# r8_2.net
KiCad netlist of a schematic drawn in EAGLE
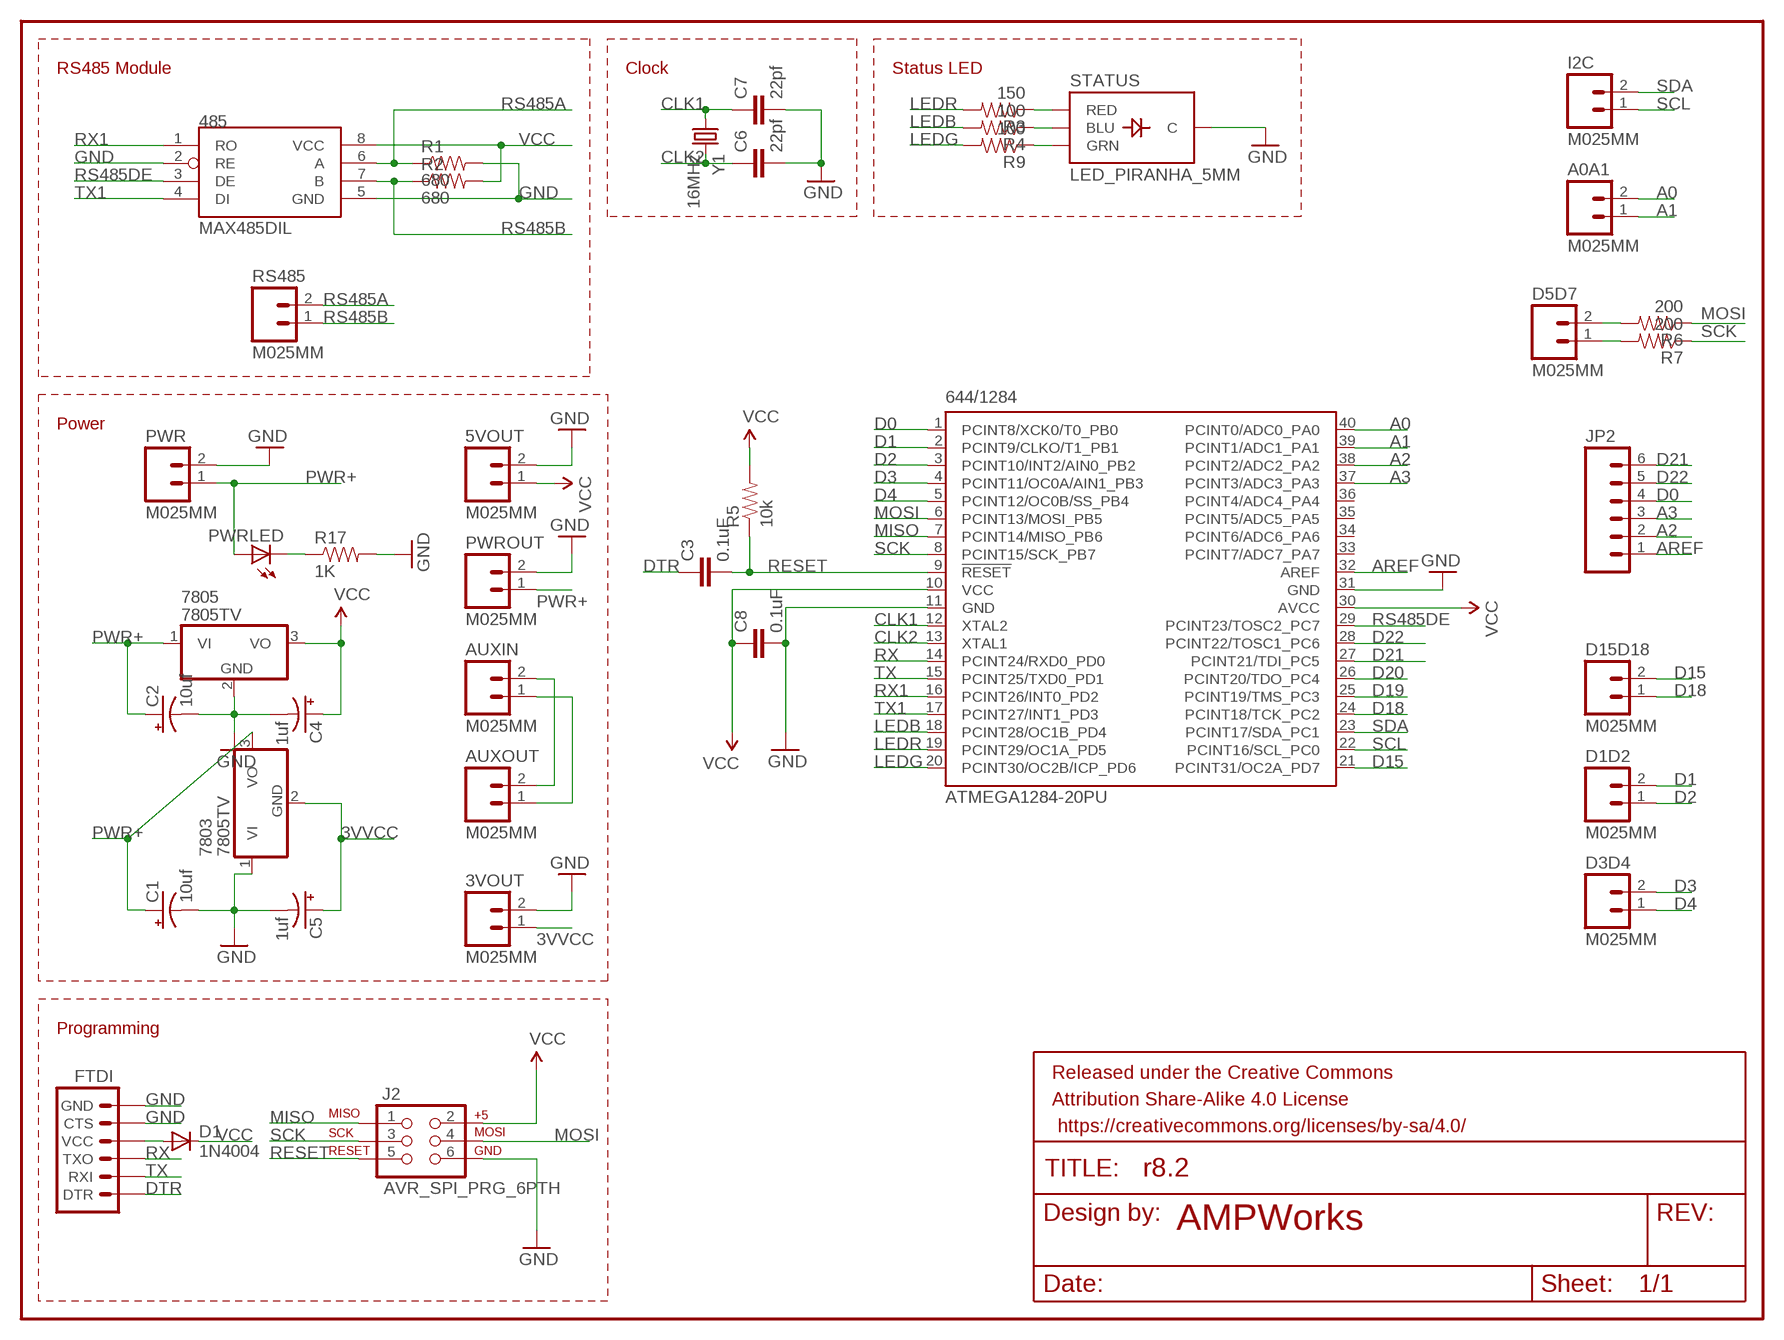
[diagram p0: schematic, sheet 1]

(export (version "E")
  (design (tool "Eeschema 10.0.6"))
  (components
    (comp (ref "3VOUT")
      (value "M025MM")
      (footprint "eagle-import:SCREWTERMINAL-5MM-2")
      (libsource (lib "eagle-import") (part "M025MM"))
    )
    (comp (ref "5VOUT")
      (value "M025MM")
      (footprint "eagle-import:SCREWTERMINAL-5MM-2")
      (libsource (lib "eagle-import") (part "M025MM"))
    )
    (comp (ref "485")
      (value "MAX485DIL")
      (footprint "eagle-import:DIL08")
      (libsource (lib "eagle-import") (part "MAX485DIL"))
    )
    (comp (ref "644/1284")
      (value "ATMEGA1284-20PU")
      (footprint "eagle-import:DIL40")
      (fields (field (name "MPN") "ATMEGA644-20PU"))
      (libsource (lib "eagle-import") (part "ATMEGA644-PU20"))
    )
    (comp (ref "7803")
      (value "7805TV")
      (footprint "eagle-import:TO220V")
      (libsource (lib "eagle-import") (part "78TV05"))
    )
    (comp (ref "7805")
      (value "7805TV")
      (footprint "eagle-import:TO220V")
      (libsource (lib "eagle-import") (part "78TV05"))
    )
    (comp (ref "A0A1")
      (value "M025MM")
      (footprint "eagle-import:SCREWTERMINAL-5MM-2")
      (libsource (lib "eagle-import") (part "M025MM"))
    )
    (comp (ref "AUXIN")
      (value "M025MM")
      (footprint "eagle-import:SCREWTERMINAL-5MM-2")
      (libsource (lib "eagle-import") (part "M025MM"))
    )
    (comp (ref "AUXOUT")
      (value "M025MM")
      (footprint "eagle-import:SCREWTERMINAL-5MM-2")
      (libsource (lib "eagle-import") (part "M025MM"))
    )
    (comp (ref "C1")
      (value "10uf")
      (footprint "eagle-import:CPOL-RADIAL-10UF-25V")
      (libsource (lib "eagle-import") (part "CAP_POLPTH2"))
    )
    (comp (ref "C2")
      (value "10uf")
      (footprint "eagle-import:CPOL-RADIAL-10UF-25V")
      (libsource (lib "eagle-import") (part "CAP_POLPTH2"))
    )
    (comp (ref "C3")
      (value "0.1uF")
      (footprint "eagle-import:CAP-PTH-SMALL")
      (libsource (lib "eagle-import") (part "CAPPTH"))
    )
    (comp (ref "C4")
      (value "1uf")
      (footprint "eagle-import:CPOL-RADIAL-10UF-25V")
      (libsource (lib "eagle-import") (part "CAP_POLPTH2"))
    )
    (comp (ref "C5")
      (value "1uf")
      (footprint "eagle-import:CPOL-RADIAL-10UF-25V")
      (libsource (lib "eagle-import") (part "CAP_POLPTH2"))
    )
    (comp (ref "C6")
      (value "22pf")
      (footprint "eagle-import:CAP-PTH-SMALL")
      (libsource (lib "eagle-import") (part "CAPPTH"))
    )
    (comp (ref "C7")
      (value "22pf")
      (footprint "eagle-import:CAP-PTH-SMALL")
      (libsource (lib "eagle-import") (part "CAPPTH"))
    )
    (comp (ref "C8")
      (value "0.1uF")
      (footprint "eagle-import:CAP-PTH-SMALL")
      (libsource (lib "eagle-import") (part "CAPPTH"))
    )
    (comp (ref "D1")
      (value "1N4004")
      (footprint "eagle-import:DO41-10")
      (libsource (lib "eagle-import") (part "1N4004"))
    )
    (comp (ref "D1D2")
      (value "M025MM")
      (footprint "eagle-import:SCREWTERMINAL-5MM-2")
      (libsource (lib "eagle-import") (part "M025MM"))
    )
    (comp (ref "D3D4")
      (value "M025MM")
      (footprint "eagle-import:SCREWTERMINAL-5MM-2")
      (libsource (lib "eagle-import") (part "M025MM"))
    )
    (comp (ref "D5D7")
      (value "M025MM")
      (footprint "eagle-import:SCREWTERMINAL-5MM-2")
      (libsource (lib "eagle-import") (part "M025MM"))
    )
    (comp (ref "D15D18")
      (value "M025MM")
      (footprint "eagle-import:SCREWTERMINAL-5MM-2")
      (libsource (lib "eagle-import") (part "M025MM"))
    )
    (comp (ref "FRAME1")
      (value "FRAME-LETTER")
      (footprint "eagle-import:CREATIVE_COMMONS")
      (libsource (lib "eagle-import") (part "FRAME-LETTER"))
    )
    (comp (ref "FTDI")
      (value "ARDUINO_SERIAL_PROGRAMPTH")
      (footprint "eagle-import:1X06")
      (libsource (lib "eagle-import") (part "ARDUINO_SERIAL_PROGRAMPTH"))
    )
    (comp (ref "I2C")
      (value "M025MM")
      (footprint "eagle-import:SCREWTERMINAL-5MM-2")
      (libsource (lib "eagle-import") (part "M025MM"))
    )
    (comp (ref "J2")
      (value "AVR_SPI_PRG_6PTH")
      (footprint "eagle-import:2X3")
      (libsource (lib "eagle-import") (part "AVR_SPI_PRG_6PTH"))
    )
    (comp (ref "JP2")
      (value "M06NO_SILK")
      (footprint "eagle-import:1X06_NO_SILK")
      (libsource (lib "eagle-import") (part "M06NO_SILK"))
    )
    (comp (ref "PWR")
      (value "M025MM")
      (footprint "eagle-import:SCREWTERMINAL-5MM-2")
      (libsource (lib "eagle-import") (part "M025MM"))
    )
    (comp (ref "PWRLED")
      (value "LED5MM")
      (footprint "eagle-import:LED5MM")
      (libsource (lib "eagle-import") (part "LED5MM"))
    )
    (comp (ref "PWROUT")
      (value "M025MM")
      (footprint "eagle-import:SCREWTERMINAL-5MM-2")
      (libsource (lib "eagle-import") (part "M025MM"))
    )
    (comp (ref "R1")
      (value "680")
      (footprint "eagle-import:AXIAL-0.4")
      (libsource (lib "eagle-import") (part "SparkFun-Resistors_RESISTORPTH-1/4W"))
    )
    (comp (ref "R2")
      (value "680")
      (footprint "eagle-import:AXIAL-0.4")
      (libsource (lib "eagle-import") (part "SparkFun-Resistors_RESISTORPTH-1/4W"))
    )
    (comp (ref "R3")
      (value "150")
      (footprint "eagle-import:AXIAL-0.4")
      (libsource (lib "eagle-import") (part "RESISTORPTH-1/4W"))
    )
    (comp (ref "R4")
      (value "100")
      (footprint "eagle-import:AXIAL-0.4")
      (libsource (lib "eagle-import") (part "RESISTORPTH-1/4W"))
    )
    (comp (ref "R5")
      (value "10k")
      (footprint "eagle-import:AXIAL-0.4")
      (libsource (lib "eagle-import") (part "RESISTORPTH-1/4W"))
    )
    (comp (ref "R6")
      (value "200")
      (footprint "eagle-import:AXIAL-0.4")
      (libsource (lib "eagle-import") (part "RESISTORPTH-1/4W"))
    )
    (comp (ref "R7")
      (value "200")
      (footprint "eagle-import:AXIAL-0.4")
      (libsource (lib "eagle-import") (part "RESISTORPTH-1/4W"))
    )
    (comp (ref "R9")
      (value "100")
      (footprint "eagle-import:AXIAL-0.4")
      (libsource (lib "eagle-import") (part "RESISTORPTH-1/4W"))
    )
    (comp (ref "R17")
      (value "1K")
      (footprint "eagle-import:AXIAL-0.4")
      (libsource (lib "eagle-import") (part "SparkFun-Resistors_RESISTORPTH-1/4W"))
    )
    (comp (ref "RS485")
      (value "M025MM")
      (footprint "eagle-import:SCREWTERMINAL-5MM-2")
      (libsource (lib "eagle-import") (part "M025MM"))
    )
    (comp (ref "STATUS")
      (value "LED_PIRANHA_5MM")
      (footprint "eagle-import:LED_PIRANHA_5MM")
      (libsource (lib "eagle-import") (part "LED_PIRANHA_5MM"))
    )
    (comp (ref "Y1")
      (value "16MHz")
      (footprint "eagle-import:HC49US")
      (libsource (lib "eagle-import") (part "CRYSTALHC49US"))
    )
  )
  (nets
    (net (code "1") (name "/3VVCC") (class "Default")
      (node (ref "3VOUT") (pin "1") (pinfunction "1_1") (pintype "passive"))
      (node (ref "7803") (pin "2") (pinfunction "GND_2") (pintype "passive"))
      (node (ref "C5") (pin "1") (pinfunction "+_1") (pintype "passive"))
    )
    (net (code "2") (name "/A0") (class "Default")
      (node (ref "644/1284") (pin "40") (pinfunction "PCINT0/ADC0_PA0_40") (pintype "bidirectional"))
      (node (ref "A0A1") (pin "2") (pinfunction "2_2") (pintype "passive"))
    )
    (net (code "3") (name "/A1") (class "Default")
      (node (ref "644/1284") (pin "39") (pinfunction "PCINT1/ADC1_PA1_39") (pintype "bidirectional"))
      (node (ref "A0A1") (pin "1") (pinfunction "1_1") (pintype "passive"))
    )
    (net (code "4") (name "/A2") (class "Default")
      (node (ref "644/1284") (pin "38") (pinfunction "PCINT2/ADC2_PA2_38") (pintype "bidirectional"))
      (node (ref "JP2") (pin "2") (pinfunction "2_2") (pintype "passive"))
    )
    (net (code "5") (name "/A3") (class "Default")
      (node (ref "644/1284") (pin "37") (pinfunction "PCINT3/ADC3_PA3_37") (pintype "bidirectional"))
      (node (ref "JP2") (pin "3") (pinfunction "3_3") (pintype "passive"))
    )
    (net (code "6") (name "/AREF") (class "Default")
      (node (ref "644/1284") (pin "32") (pinfunction "AREF_32") (pintype "passive"))
      (node (ref "JP2") (pin "1") (pinfunction "1_1") (pintype "passive"))
    )
    (net (code "7") (name "/CLK1") (class "Default")
      (node (ref "644/1284") (pin "12") (pinfunction "XTAL2_12") (pintype "output"))
      (node (ref "C7") (pin "1") (pinfunction "1_1") (pintype "passive"))
      (node (ref "Y1") (pin "1") (pinfunction "1_1") (pintype "passive"))
    )
    (net (code "8") (name "/CLK2") (class "Default")
      (node (ref "644/1284") (pin "13") (pinfunction "XTAL1_13") (pintype "input"))
      (node (ref "C6") (pin "1") (pinfunction "1_1") (pintype "passive"))
      (node (ref "Y1") (pin "2") (pinfunction "2_2") (pintype "passive"))
    )
    (net (code "9") (name "/D0") (class "Default")
      (node (ref "644/1284") (pin "1") (pinfunction "PCINT8/XCK0/T0_PB0_1") (pintype "bidirectional"))
      (node (ref "JP2") (pin "4") (pinfunction "4_4") (pintype "passive"))
    )
    (net (code "10") (name "/D1") (class "Default")
      (node (ref "644/1284") (pin "2") (pinfunction "PCINT9/CLKO/T1_PB1_2") (pintype "bidirectional"))
      (node (ref "D1D2") (pin "2") (pinfunction "2_2") (pintype "passive"))
    )
    (net (code "11") (name "/D2") (class "Default")
      (node (ref "644/1284") (pin "3") (pinfunction "PCINT10/INT2/AIN0_PB2_3") (pintype "bidirectional"))
      (node (ref "D1D2") (pin "1") (pinfunction "1_1") (pintype "passive"))
    )
    (net (code "12") (name "/D3") (class "Default")
      (node (ref "644/1284") (pin "4") (pinfunction "PCINT11/OC0A/AIN1_PB3_4") (pintype "bidirectional"))
      (node (ref "D3D4") (pin "2") (pinfunction "2_2") (pintype "passive"))
    )
    (net (code "13") (name "/D4") (class "Default")
      (node (ref "644/1284") (pin "5") (pinfunction "PCINT12/OC0B/SS_PB4_5") (pintype "bidirectional"))
      (node (ref "D3D4") (pin "1") (pinfunction "1_1") (pintype "passive"))
    )
    (net (code "14") (name "/D15") (class "Default")
      (node (ref "644/1284") (pin "21") (pinfunction "PCINT31/OC2A_PD7_21") (pintype "bidirectional"))
      (node (ref "D15D18") (pin "2") (pinfunction "2_2") (pintype "passive"))
    )
    (net (code "15") (name "/D18") (class "Default")
      (node (ref "644/1284") (pin "24") (pinfunction "PCINT18/TCK_PC2_24") (pintype "bidirectional"))
      (node (ref "D15D18") (pin "1") (pinfunction "1_1") (pintype "passive"))
    )
    (net (code "16") (name "/D19") (class "Default")
      (node (ref "644/1284") (pin "25") (pinfunction "PCINT19/TMS_PC3_25") (pintype "bidirectional"))
    )
    (net (code "17") (name "/D20") (class "Default")
      (node (ref "644/1284") (pin "26") (pinfunction "PCINT20/TDO_PC4_26") (pintype "bidirectional"))
    )
    (net (code "18") (name "/D21") (class "Default")
      (node (ref "644/1284") (pin "27") (pinfunction "PCINT21/TDI_PC5_27") (pintype "bidirectional"))
      (node (ref "JP2") (pin "6") (pinfunction "6_6") (pintype "passive"))
    )
    (net (code "19") (name "/D22") (class "Default")
      (node (ref "644/1284") (pin "28") (pinfunction "PCINT22/TOSC1_PC6_28") (pintype "bidirectional"))
      (node (ref "JP2") (pin "5") (pinfunction "5_5") (pintype "passive"))
    )
    (net (code "20") (name "/DTR") (class "Default")
      (node (ref "C3") (pin "1") (pinfunction "1_1") (pintype "passive"))
      (node (ref "FTDI") (pin "DTR") (pinfunction "DTR_DTR") (pintype "passive"))
    )
    (net (code "21") (name "/LEDB") (class "Default")
      (node (ref "644/1284") (pin "18") (pinfunction "PCINT28/OC1B_PD4_18") (pintype "bidirectional"))
      (node (ref "R4") (pin "P$2") (pinfunction "2_P$2") (pintype "passive"))
    )
    (net (code "22") (name "/LEDG") (class "Default")
      (node (ref "644/1284") (pin "20") (pinfunction "PCINT30/OC2B/ICP_PD6_20") (pintype "bidirectional"))
      (node (ref "R9") (pin "P$2") (pinfunction "2_P$2") (pintype "passive"))
    )
    (net (code "23") (name "/LEDR") (class "Default")
      (node (ref "644/1284") (pin "19") (pinfunction "PCINT29/OC1A_PD5_19") (pintype "bidirectional"))
      (node (ref "R3") (pin "P$2") (pinfunction "2_P$2") (pintype "passive"))
    )
    (net (code "24") (name "/MISO") (class "Default")
      (node (ref "644/1284") (pin "7") (pinfunction "PCINT14/MISO_PB6_7") (pintype "bidirectional"))
      (node (ref "J2") (pin "1") (pinfunction "1_1") (pintype "passive"))
    )
    (net (code "25") (name "/MOSI") (class "Default")
      (node (ref "644/1284") (pin "6") (pinfunction "PCINT13/MOSI_PB5_6") (pintype "bidirectional"))
      (node (ref "J2") (pin "4") (pinfunction "4_4") (pintype "passive"))
      (node (ref "R6") (pin "P$1") (pinfunction "1_P$1") (pintype "passive"))
    )
    (net (code "26") (name "/PWR+") (class "Default")
      (node (ref "7803") (pin "3") (pinfunction "VO_3") (pintype "passive"))
      (node (ref "7805") (pin "1") (pinfunction "VI_1") (pintype "input"))
      (node (ref "C1") (pin "1") (pinfunction "+_1") (pintype "passive"))
      (node (ref "C2") (pin "1") (pinfunction "+_1") (pintype "passive"))
      (node (ref "PWR") (pin "1") (pinfunction "1_1") (pintype "passive"))
      (node (ref "PWRLED") (pin "A") (pinfunction "A_A") (pintype "passive"))
      (node (ref "PWROUT") (pin "1") (pinfunction "1_1") (pintype "passive"))
    )
    (net (code "27") (name "/RESET") (class "Default")
      (node (ref "644/1284") (pin "9") (pinfunction "~{RESET}_9") (pintype "input"))
      (node (ref "C3") (pin "2") (pinfunction "2_2") (pintype "passive"))
      (node (ref "J2") (pin "5") (pinfunction "5_5") (pintype "passive"))
      (node (ref "R5") (pin "P$1") (pinfunction "1_P$1") (pintype "passive"))
    )
    (net (code "28") (name "/RS485A") (class "Default")
      (node (ref "485") (pin "6") (pinfunction "A_6") (pintype "bidirectional"))
      (node (ref "R1") (pin "P$1") (pinfunction "1_P$1") (pintype "passive"))
      (node (ref "RS485") (pin "2") (pinfunction "2_2") (pintype "passive"))
    )
    (net (code "29") (name "/RS485B") (class "Default")
      (node (ref "485") (pin "7") (pinfunction "B_7") (pintype "bidirectional"))
      (node (ref "R2") (pin "P$1") (pinfunction "1_P$1") (pintype "passive"))
      (node (ref "RS485") (pin "1") (pinfunction "1_1") (pintype "passive"))
    )
    (net (code "30") (name "/RS485DE") (class "Default")
      (node (ref "485") (pin "3") (pinfunction "DE_3") (pintype "bidirectional"))
      (node (ref "644/1284") (pin "29") (pinfunction "PCINT23/TOSC2_PC7_29") (pintype "bidirectional"))
    )
    (net (code "31") (name "/RX") (class "Default")
      (node (ref "644/1284") (pin "14") (pinfunction "PCINT24/RXD0_PD0_14") (pintype "bidirectional"))
      (node (ref "FTDI") (pin "TXO") (pinfunction "TXO_TXO") (pintype "passive"))
    )
    (net (code "32") (name "/RX1") (class "Default")
      (node (ref "485") (pin "1") (pinfunction "RO_1") (pintype "bidirectional"))
      (node (ref "644/1284") (pin "16") (pinfunction "PCINT26/INT0_PD2_16") (pintype "bidirectional"))
    )
    (net (code "33") (name "/SCK") (class "Default")
      (node (ref "644/1284") (pin "8") (pinfunction "PCINT15/SCK_PB7_8") (pintype "bidirectional"))
      (node (ref "J2") (pin "3") (pinfunction "3_3") (pintype "passive"))
      (node (ref "R7") (pin "P$1") (pinfunction "1_P$1") (pintype "passive"))
    )
    (net (code "34") (name "/SCL") (class "Default")
      (node (ref "644/1284") (pin "22") (pinfunction "PCINT16/SCL_PC0_22") (pintype "bidirectional"))
      (node (ref "I2C") (pin "1") (pinfunction "1_1") (pintype "passive"))
    )
    (net (code "35") (name "/SDA") (class "Default")
      (node (ref "644/1284") (pin "23") (pinfunction "PCINT17/SDA_PC1_23") (pintype "bidirectional"))
      (node (ref "I2C") (pin "2") (pinfunction "2_2") (pintype "passive"))
    )
    (net (code "36") (name "/TX") (class "Default")
      (node (ref "644/1284") (pin "15") (pinfunction "PCINT25/TXD0_PD1_15") (pintype "bidirectional"))
      (node (ref "FTDI") (pin "RXI") (pinfunction "RXI_RXI") (pintype "passive"))
    )
    (net (code "37") (name "/TX1") (class "Default")
      (node (ref "485") (pin "4") (pinfunction "DI_4") (pintype "bidirectional"))
      (node (ref "644/1284") (pin "17") (pinfunction "PCINT27/INT1_PD3_17") (pintype "bidirectional"))
    )
    (net (code "38") (name "GND") (class "Default")
      (node (ref "3VOUT") (pin "2") (pinfunction "2_2") (pintype "passive"))
      (node (ref "485") (pin "2") (pinfunction "RE_2") (pintype "bidirectional"))
      (node (ref "485") (pin "5") (pinfunction "GND_5") (pintype "bidirectional"))
      (node (ref "5VOUT") (pin "2") (pinfunction "2_2") (pintype "passive"))
      (node (ref "644/1284") (pin "11") (pinfunction "GND_11") (pintype "power_in"))
      (node (ref "644/1284") (pin "31") (pinfunction "GND_31") (pintype "power_in"))
      (node (ref "7803") (pin "1") (pinfunction "VI_1") (pintype "input"))
      (node (ref "7805") (pin "2") (pinfunction "GND_2") (pintype "passive"))
      (node (ref "C1") (pin "2") (pinfunction "-_2") (pintype "passive"))
      (node (ref "C2") (pin "2") (pinfunction "-_2") (pintype "passive"))
      (node (ref "C4") (pin "2") (pinfunction "-_2") (pintype "passive"))
      (node (ref "C5") (pin "2") (pinfunction "-_2") (pintype "passive"))
      (node (ref "C6") (pin "2") (pinfunction "2_2") (pintype "passive"))
      (node (ref "C7") (pin "2") (pinfunction "2_2") (pintype "passive"))
      (node (ref "C8") (pin "2") (pinfunction "2_2") (pintype "passive"))
      (node (ref "FTDI") (pin "CTS") (pinfunction "CTS_CTS") (pintype "passive"))
      (node (ref "FTDI") (pin "GND") (pinfunction "GND_GND") (pintype "passive"))
      (node (ref "J2") (pin "6") (pinfunction "6_6") (pintype "passive"))
      (node (ref "PWR") (pin "2") (pinfunction "2_2") (pintype "passive"))
      (node (ref "PWROUT") (pin "2") (pinfunction "2_2") (pintype "passive"))
      (node (ref "R1") (pin "P$2") (pinfunction "2_P$2") (pintype "passive"))
      (node (ref "R17") (pin "P$2") (pinfunction "2_P$2") (pintype "passive"))
      (node (ref "STATUS") (pin "-") (pinfunction "C_-") (pintype "bidirectional"))
    )
    (net (code "39") (name "Net-(AUXIN-Pad1)") (class "Default")
      (node (ref "AUXIN") (pin "1") (pinfunction "1_1") (pintype "passive"))
      (node (ref "AUXOUT") (pin "1") (pinfunction "1_1") (pintype "passive"))
    )
    (net (code "40") (name "Net-(AUXIN-Pad2)") (class "Default")
      (node (ref "AUXIN") (pin "2") (pinfunction "2_2") (pintype "passive"))
      (node (ref "AUXOUT") (pin "2") (pinfunction "2_2") (pintype "passive"))
    )
    (net (code "41") (name "Net-(D1-PadA)") (class "Default")
      (node (ref "D1") (pin "A") (pinfunction "A_A") (pintype "passive"))
      (node (ref "FTDI") (pin "VCC") (pinfunction "VCC_VCC") (pintype "passive"))
    )
    (net (code "42") (name "Net-(PWRLED-C)") (class "Default")
      (node (ref "PWRLED") (pin "K") (pinfunction "C_K") (pintype "passive"))
      (node (ref "R17") (pin "P$1") (pinfunction "1_P$1") (pintype "passive"))
    )
    (net (code "43") (name "Net-(R3-1)") (class "Default")
      (node (ref "R3") (pin "P$1") (pinfunction "1_P$1") (pintype "passive"))
      (node (ref "STATUS") (pin "R") (pinfunction "RED_R") (pintype "bidirectional"))
    )
    (net (code "44") (name "Net-(R4-1)") (class "Default")
      (node (ref "R4") (pin "P$1") (pinfunction "1_P$1") (pintype "passive"))
      (node (ref "STATUS") (pin "B") (pinfunction "BLU_B") (pintype "bidirectional"))
    )
    (net (code "45") (name "Net-(R6-2)") (class "Default")
      (node (ref "D5D7") (pin "2") (pinfunction "2_2") (pintype "passive"))
      (node (ref "R6") (pin "P$2") (pinfunction "2_P$2") (pintype "passive"))
    )
    (net (code "46") (name "Net-(R7-2)") (class "Default")
      (node (ref "D5D7") (pin "1") (pinfunction "1_1") (pintype "passive"))
      (node (ref "R7") (pin "P$2") (pinfunction "2_P$2") (pintype "passive"))
    )
    (net (code "47") (name "Net-(R9-1)") (class "Default")
      (node (ref "R9") (pin "P$1") (pinfunction "1_P$1") (pintype "passive"))
      (node (ref "STATUS") (pin "G") (pinfunction "GRN_G") (pintype "bidirectional"))
    )
    (net (code "48") (name "VCC") (class "Default")
      (node (ref "485") (pin "8") (pinfunction "VCC_8") (pintype "bidirectional"))
      (node (ref "5VOUT") (pin "1") (pinfunction "1_1") (pintype "passive"))
      (node (ref "644/1284") (pin "10") (pinfunction "VCC_10") (pintype "power_in"))
      (node (ref "644/1284") (pin "30") (pinfunction "AVCC_30") (pintype "power_in"))
      (node (ref "7805") (pin "3") (pinfunction "VO_3") (pintype "passive"))
      (node (ref "C4") (pin "1") (pinfunction "+_1") (pintype "passive"))
      (node (ref "C8") (pin "1") (pinfunction "1_1") (pintype "passive"))
      (node (ref "D1") (pin "C") (pinfunction "C_C") (pintype "passive"))
      (node (ref "J2") (pin "2") (pinfunction "2_2") (pintype "passive"))
      (node (ref "R2") (pin "P$2") (pinfunction "2_P$2") (pintype "passive"))
      (node (ref "R5") (pin "P$2") (pinfunction "2_P$2") (pintype "passive"))
    )
    (net (code "49") (name "unconnected-(644/1284-PCINT4{slash}ADC4_PA4-Pad36)") (class "Default")
      (node (ref "644/1284") (pin "36") (pinfunction "PCINT4/ADC4_PA4_36") (pintype "bidirectional"))
    )
    (net (code "50") (name "unconnected-(644/1284-PCINT5{slash}ADC5_PA5-Pad35)") (class "Default")
      (node (ref "644/1284") (pin "35") (pinfunction "PCINT5/ADC5_PA5_35") (pintype "bidirectional"))
    )
    (net (code "51") (name "unconnected-(644/1284-PCINT6{slash}ADC6_PA6-Pad34)") (class "Default")
      (node (ref "644/1284") (pin "34") (pinfunction "PCINT6/ADC6_PA6_34") (pintype "bidirectional"))
    )
    (net (code "52") (name "unconnected-(644/1284-PCINT7{slash}ADC7_PA7-Pad33)") (class "Default")
      (node (ref "644/1284") (pin "33") (pinfunction "PCINT7/ADC7_PA7_33") (pintype "bidirectional"))
    )
  )
)
